# adafruit_oled_featherwing.net
KiCad netlist of a schematic drawn in EAGLE
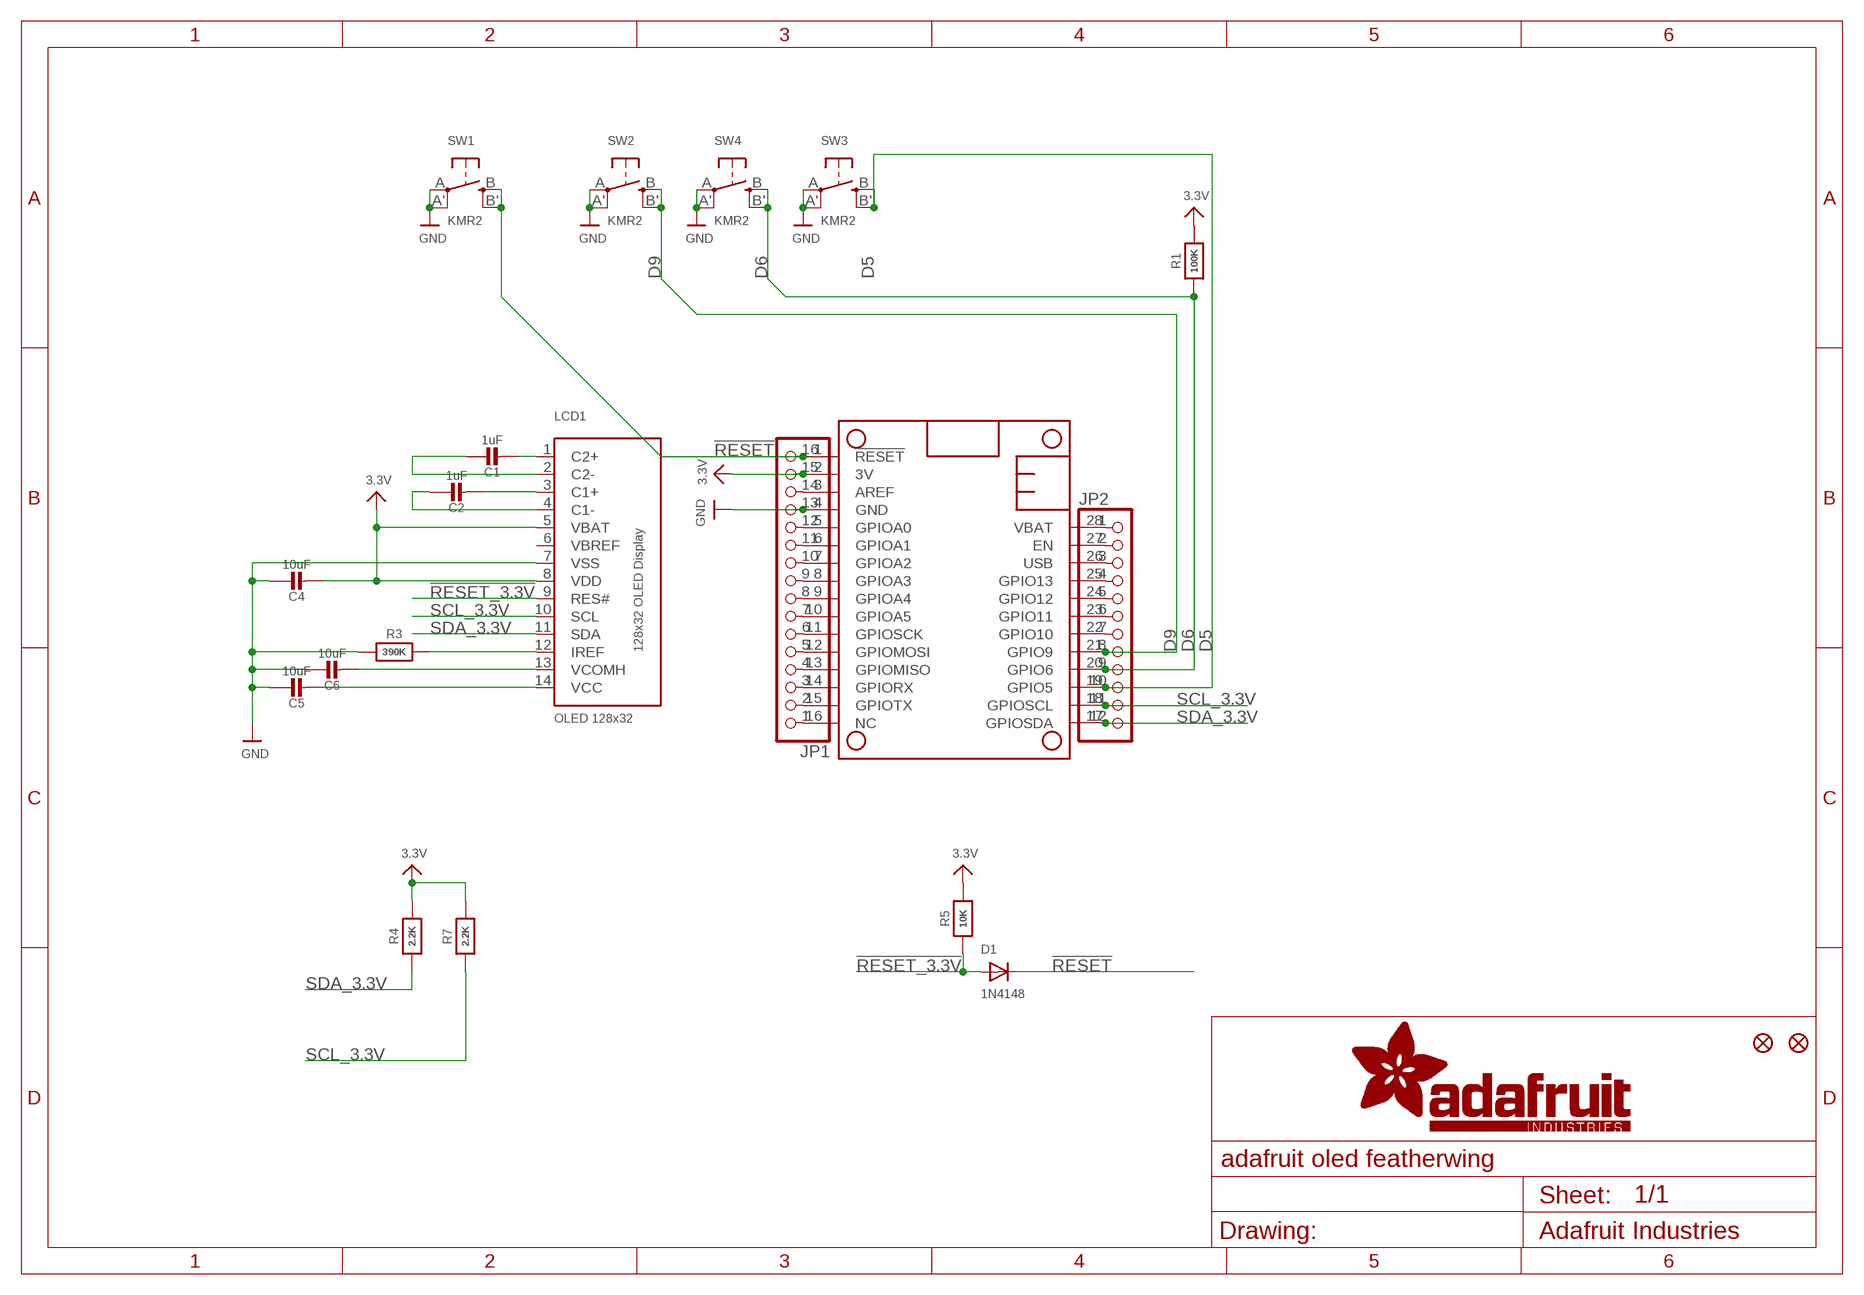
[diagram p0: schematic, sheet 1]

(export (version "E")
  (design (tool "Eeschema 10.0.6"))
  (components
    (comp (ref "C1")
      (value "1uF")
      (footprint "eagle-import:0805-NO")
      (libsource (lib "eagle-import") (part "CAP_CERAMIC0805-NOOUTLINE"))
    )
    (comp (ref "C2")
      (value "1uF")
      (footprint "eagle-import:0805-NO")
      (libsource (lib "eagle-import") (part "CAP_CERAMIC0805-NOOUTLINE"))
    )
    (comp (ref "C4")
      (value "10uF")
      (footprint "eagle-import:0805-NO")
      (libsource (lib "eagle-import") (part "CAP_CERAMIC0805-NOOUTLINE"))
    )
    (comp (ref "C5")
      (value "10uF")
      (footprint "eagle-import:0805-NO")
      (libsource (lib "eagle-import") (part "CAP_CERAMIC0805-NOOUTLINE"))
    )
    (comp (ref "C6")
      (value "10uF")
      (footprint "eagle-import:0805-NO")
      (libsource (lib "eagle-import") (part "CAP_CERAMIC0805-NOOUTLINE"))
    )
    (comp (ref "D1")
      (value "1N4148")
      (footprint "eagle-import:SOD-323F")
      (libsource (lib "eagle-import") (part "DIODESOD-323F"))
    )
    (comp (ref "FID1")
      (value "FIDUCIAL\"\"")
      (footprint "eagle-import:FIDUCIAL_1MM")
      (libsource (lib "eagle-import") (part "FIDUCIAL{dblquote}{dblquote}"))
    )
    (comp (ref "FID2")
      (value "FIDUCIAL\"\"")
      (footprint "eagle-import:FIDUCIAL_1MM")
      (libsource (lib "eagle-import") (part "FIDUCIAL{dblquote}{dblquote}"))
    )
    (comp (ref "JP1")
      (value "HEADER-1X16ROUND")
      (footprint "eagle-import:1X16_ROUND")
      (libsource (lib "eagle-import") (part "HEADER-1X16ROUND"))
    )
    (comp (ref "JP2")
      (value "HEADER-1X12")
      (footprint "eagle-import:1X12_ROUND")
      (libsource (lib "eagle-import") (part "HEADER-1X12"))
    )
    (comp (ref "LCD1")
      (value "OLED 128x32")
      (footprint "eagle-import:UG-2832HSWEG02_WRAPUNDER")
      (libsource (lib "eagle-import") (part "DISP_OLED_UG-2832HSWEG02"))
    )
    (comp (ref "MS1")
      (value "FEATHERWING")
      (footprint "eagle-import:FEATHERWING")
      (libsource (lib "eagle-import") (part "FEATHERWING"))
    )
    (comp (ref "R1")
      (value "100K")
      (footprint "eagle-import:_0805MP")
      (libsource (lib "eagle-import") (part "RESISTOR_0805MP"))
    )
    (comp (ref "R3")
      (value "390K")
      (footprint "eagle-import:0805-NO")
      (libsource (lib "eagle-import") (part "RESISTOR0805_NOOUTLINE"))
    )
    (comp (ref "R4")
      (value "2.2K")
      (footprint "eagle-import:0805-NO")
      (libsource (lib "eagle-import") (part "RESISTOR0805_NOOUTLINE"))
    )
    (comp (ref "R5")
      (value "10K")
      (footprint "eagle-import:0805-NO")
      (libsource (lib "eagle-import") (part "RESISTOR0805_NOOUTLINE"))
    )
    (comp (ref "R7")
      (value "2.2K")
      (footprint "eagle-import:0805-NO")
      (libsource (lib "eagle-import") (part "RESISTOR0805_NOOUTLINE"))
    )
    (comp (ref "SW1")
      (value "KMR2")
      (footprint "eagle-import:BTN_KMR2_4.6X2.8")
      (libsource (lib "eagle-import") (part "SWITCH_TACT_SMT4.6X2.8"))
    )
    (comp (ref "SW2")
      (value "KMR2")
      (footprint "eagle-import:BTN_KMR2_4.6X2.8")
      (libsource (lib "eagle-import") (part "SWITCH_TACT_SMT4.6X2.8"))
    )
    (comp (ref "SW3")
      (value "KMR2")
      (footprint "eagle-import:BTN_KMR2_4.6X2.8")
      (libsource (lib "eagle-import") (part "SWITCH_TACT_SMT4.6X2.8"))
    )
    (comp (ref "SW4")
      (value "KMR2")
      (footprint "eagle-import:BTN_KMR2_4.6X2.8")
      (libsource (lib "eagle-import") (part "SWITCH_TACT_SMT4.6X2.8"))
    )
  )
  (nets
    (net (code "1") (name "/D5") (class "Default")
      (node (ref "JP2") (pin "10") (pinfunction "10_10") (pintype "passive"))
      (node (ref "MS1") (pin "19") (pinfunction "GPIO5_19") (pintype "bidirectional"))
      (node (ref "SW3") (pin "B") (pinfunction "S_B") (pintype "passive"))
      (node (ref "SW3") (pin "B'") (pinfunction "S1_B'") (pintype "passive"))
    )
    (net (code "2") (name "/D6") (class "Default")
      (node (ref "JP2") (pin "9") (pinfunction "9_9") (pintype "passive"))
      (node (ref "MS1") (pin "20") (pinfunction "GPIO6_20") (pintype "bidirectional"))
      (node (ref "R1") (pin "1") (pinfunction "1_1") (pintype "passive"))
      (node (ref "SW4") (pin "B") (pinfunction "S_B") (pintype "passive"))
      (node (ref "SW4") (pin "B'") (pinfunction "S1_B'") (pintype "passive"))
    )
    (net (code "3") (name "/D9") (class "Default")
      (node (ref "JP2") (pin "8") (pinfunction "8_8") (pintype "passive"))
      (node (ref "MS1") (pin "21") (pinfunction "GPIO9_21") (pintype "bidirectional"))
      (node (ref "SW2") (pin "B") (pinfunction "S_B") (pintype "passive"))
      (node (ref "SW2") (pin "B'") (pinfunction "S1_B'") (pintype "passive"))
    )
    (net (code "4") (name "/SCL_3.3V") (class "Default")
      (node (ref "JP2") (pin "11") (pinfunction "11_11") (pintype "passive"))
      (node (ref "LCD1") (pin "10") (pinfunction "SCL_10") (pintype "bidirectional"))
      (node (ref "MS1") (pin "18") (pinfunction "GPIOSCL_18") (pintype "bidirectional"))
      (node (ref "R7") (pin "1") (pinfunction "1_1") (pintype "passive"))
    )
    (net (code "5") (name "/SDA_3.3V") (class "Default")
      (node (ref "JP2") (pin "12") (pinfunction "12_12") (pintype "passive"))
      (node (ref "LCD1") (pin "11") (pinfunction "SDA_11") (pintype "bidirectional"))
      (node (ref "MS1") (pin "17") (pinfunction "GPIOSDA_17") (pintype "bidirectional"))
      (node (ref "R4") (pin "1") (pinfunction "1_1") (pintype "passive"))
    )
    (net (code "6") (name "/VBREF") (class "Default")
      (node (ref "LCD1") (pin "6") (pinfunction "VBREF_6") (pintype "power_in"))
    )
    (net (code "7") (name "/~{RESET_3.3V}") (class "Default")
      (node (ref "D1") (pin "A") (pinfunction "A_A") (pintype "passive"))
      (node (ref "LCD1") (pin "9") (pinfunction "RES#_9") (pintype "bidirectional"))
      (node (ref "R5") (pin "1") (pinfunction "1_1") (pintype "passive"))
    )
    (net (code "8") (name "/~{RESET}") (class "Default")
      (node (ref "D1") (pin "C") (pinfunction "C_C") (pintype "passive"))
      (node (ref "JP1") (pin "16") (pinfunction "16_16") (pintype "passive"))
      (node (ref "MS1") (pin "1") (pinfunction "~{RESET}_1") (pintype "input"))
      (node (ref "SW1") (pin "B") (pinfunction "S_B") (pintype "passive"))
      (node (ref "SW1") (pin "B'") (pinfunction "S1_B'") (pintype "passive"))
    )
    (net (code "9") (name "3.3V") (class "Default")
      (node (ref "C4") (pin "2") (pinfunction "2_2") (pintype "passive"))
      (node (ref "JP1") (pin "15") (pinfunction "15_15") (pintype "passive"))
      (node (ref "LCD1") (pin "5") (pinfunction "VBAT_5") (pintype "power_in"))
      (node (ref "LCD1") (pin "8") (pinfunction "VDD_8") (pintype "power_in"))
      (node (ref "MS1") (pin "2") (pinfunction "3V_2") (pintype "power_in"))
      (node (ref "R1") (pin "2") (pinfunction "2_2") (pintype "passive"))
      (node (ref "R4") (pin "2") (pinfunction "2_2") (pintype "passive"))
      (node (ref "R5") (pin "2") (pinfunction "2_2") (pintype "passive"))
      (node (ref "R7") (pin "2") (pinfunction "2_2") (pintype "passive"))
    )
    (net (code "10") (name "GND") (class "Default")
      (node (ref "C4") (pin "1") (pinfunction "1_1") (pintype "passive"))
      (node (ref "C5") (pin "1") (pinfunction "1_1") (pintype "passive"))
      (node (ref "C6") (pin "1") (pinfunction "1_1") (pintype "passive"))
      (node (ref "JP1") (pin "13") (pinfunction "13_13") (pintype "passive"))
      (node (ref "LCD1") (pin "7") (pinfunction "VSS_7") (pintype "power_in"))
      (node (ref "MS1") (pin "4") (pinfunction "GND_4") (pintype "power_in"))
      (node (ref "R3") (pin "1") (pinfunction "1_1") (pintype "passive"))
      (node (ref "SW1") (pin "A") (pinfunction "P_A") (pintype "passive"))
      (node (ref "SW1") (pin "A'") (pinfunction "P1_A'") (pintype "passive"))
      (node (ref "SW2") (pin "A") (pinfunction "P_A") (pintype "passive"))
      (node (ref "SW2") (pin "A'") (pinfunction "P1_A'") (pintype "passive"))
      (node (ref "SW3") (pin "A") (pinfunction "P_A") (pintype "passive"))
      (node (ref "SW3") (pin "A'") (pinfunction "P1_A'") (pintype "passive"))
      (node (ref "SW4") (pin "A") (pinfunction "P_A") (pintype "passive"))
      (node (ref "SW4") (pin "A'") (pinfunction "P1_A'") (pintype "passive"))
    )
    (net (code "11") (name "Net-(LCD1-C1+)") (class "Default")
      (node (ref "C2") (pin "2") (pinfunction "2_2") (pintype "passive"))
      (node (ref "LCD1") (pin "3") (pinfunction "C1+_3") (pintype "bidirectional"))
    )
    (net (code "12") (name "Net-(LCD1-C1-)") (class "Default")
      (node (ref "C2") (pin "1") (pinfunction "1_1") (pintype "passive"))
      (node (ref "LCD1") (pin "4") (pinfunction "C1-_4") (pintype "bidirectional"))
    )
    (net (code "13") (name "Net-(LCD1-C2+)") (class "Default")
      (node (ref "C1") (pin "2") (pinfunction "2_2") (pintype "passive"))
      (node (ref "LCD1") (pin "1") (pinfunction "C2+_1") (pintype "bidirectional"))
    )
    (net (code "14") (name "Net-(LCD1-C2-)") (class "Default")
      (node (ref "C1") (pin "1") (pinfunction "1_1") (pintype "passive"))
      (node (ref "LCD1") (pin "2") (pinfunction "C2-_2") (pintype "bidirectional"))
    )
    (net (code "15") (name "Net-(LCD1-IREF)") (class "Default")
      (node (ref "LCD1") (pin "12") (pinfunction "IREF_12") (pintype "bidirectional"))
      (node (ref "R3") (pin "2") (pinfunction "2_2") (pintype "passive"))
    )
    (net (code "16") (name "Net-(LCD1-VCC)") (class "Default")
      (node (ref "C5") (pin "2") (pinfunction "2_2") (pintype "passive"))
      (node (ref "LCD1") (pin "14") (pinfunction "VCC_14") (pintype "power_in"))
    )
    (net (code "17") (name "Net-(LCD1-VCOMH)") (class "Default")
      (node (ref "C6") (pin "2") (pinfunction "2_2") (pintype "passive"))
      (node (ref "LCD1") (pin "13") (pinfunction "VCOMH_13") (pintype "power_in"))
    )
    (net (code "18") (name "Net-(MS1-AREF)") (class "Default")
      (node (ref "JP1") (pin "14") (pinfunction "14_14") (pintype "passive"))
      (node (ref "MS1") (pin "3") (pinfunction "AREF_3") (pintype "passive"))
    )
    (net (code "19") (name "Net-(MS1-EN)") (class "Default")
      (node (ref "JP2") (pin "2") (pinfunction "2_2") (pintype "passive"))
      (node (ref "MS1") (pin "27") (pinfunction "EN_27") (pintype "passive"))
    )
    (net (code "20") (name "Net-(MS1-GPIO10)") (class "Default")
      (node (ref "JP2") (pin "7") (pinfunction "7_7") (pintype "passive"))
      (node (ref "MS1") (pin "22") (pinfunction "GPIO10_22") (pintype "bidirectional"))
    )
    (net (code "21") (name "Net-(MS1-GPIO11)") (class "Default")
      (node (ref "JP2") (pin "6") (pinfunction "6_6") (pintype "passive"))
      (node (ref "MS1") (pin "23") (pinfunction "GPIO11_23") (pintype "bidirectional"))
    )
    (net (code "22") (name "Net-(MS1-GPIO12)") (class "Default")
      (node (ref "JP2") (pin "5") (pinfunction "5_5") (pintype "passive"))
      (node (ref "MS1") (pin "24") (pinfunction "GPIO12_24") (pintype "bidirectional"))
    )
    (net (code "23") (name "Net-(MS1-GPIO13)") (class "Default")
      (node (ref "JP2") (pin "4") (pinfunction "4_4") (pintype "passive"))
      (node (ref "MS1") (pin "25") (pinfunction "GPIO13_25") (pintype "bidirectional"))
    )
    (net (code "24") (name "Net-(MS1-GPIOA0)") (class "Default")
      (node (ref "JP1") (pin "12") (pinfunction "12_12") (pintype "passive"))
      (node (ref "MS1") (pin "5") (pinfunction "GPIOA0_5") (pintype "bidirectional"))
    )
    (net (code "25") (name "Net-(MS1-GPIOA1)") (class "Default")
      (node (ref "JP1") (pin "11") (pinfunction "11_11") (pintype "passive"))
      (node (ref "MS1") (pin "6") (pinfunction "GPIOA1_6") (pintype "bidirectional"))
    )
    (net (code "26") (name "Net-(MS1-GPIOA2)") (class "Default")
      (node (ref "JP1") (pin "10") (pinfunction "10_10") (pintype "passive"))
      (node (ref "MS1") (pin "7") (pinfunction "GPIOA2_7") (pintype "bidirectional"))
    )
    (net (code "27") (name "Net-(MS1-GPIOA3)") (class "Default")
      (node (ref "JP1") (pin "9") (pinfunction "9_9") (pintype "passive"))
      (node (ref "MS1") (pin "8") (pinfunction "GPIOA3_8") (pintype "bidirectional"))
    )
    (net (code "28") (name "Net-(MS1-GPIOA4)") (class "Default")
      (node (ref "JP1") (pin "8") (pinfunction "8_8") (pintype "passive"))
      (node (ref "MS1") (pin "9") (pinfunction "GPIOA4_9") (pintype "bidirectional"))
    )
    (net (code "29") (name "Net-(MS1-GPIOA5)") (class "Default")
      (node (ref "JP1") (pin "7") (pinfunction "7_7") (pintype "passive"))
      (node (ref "MS1") (pin "10") (pinfunction "GPIOA5_10") (pintype "bidirectional"))
    )
    (net (code "30") (name "Net-(MS1-GPIOMISO)") (class "Default")
      (node (ref "JP1") (pin "4") (pinfunction "4_4") (pintype "passive"))
      (node (ref "MS1") (pin "13") (pinfunction "GPIOMISO_13") (pintype "bidirectional"))
    )
    (net (code "31") (name "Net-(MS1-GPIOMOSI)") (class "Default")
      (node (ref "JP1") (pin "5") (pinfunction "5_5") (pintype "passive"))
      (node (ref "MS1") (pin "12") (pinfunction "GPIOMOSI_12") (pintype "bidirectional"))
    )
    (net (code "32") (name "Net-(MS1-GPIORX)") (class "Default")
      (node (ref "JP1") (pin "3") (pinfunction "3_3") (pintype "passive"))
      (node (ref "MS1") (pin "14") (pinfunction "GPIORX_14") (pintype "bidirectional"))
    )
    (net (code "33") (name "Net-(MS1-GPIOSCK)") (class "Default")
      (node (ref "JP1") (pin "6") (pinfunction "6_6") (pintype "passive"))
      (node (ref "MS1") (pin "11") (pinfunction "GPIOSCK_11") (pintype "bidirectional"))
    )
    (net (code "34") (name "Net-(MS1-GPIOTX)") (class "Default")
      (node (ref "JP1") (pin "2") (pinfunction "2_2") (pintype "passive"))
      (node (ref "MS1") (pin "15") (pinfunction "GPIOTX_15") (pintype "bidirectional"))
    )
    (net (code "35") (name "Net-(MS1-NC)") (class "Default")
      (node (ref "JP1") (pin "1") (pinfunction "1_1") (pintype "passive"))
      (node (ref "MS1") (pin "16") (pinfunction "NC_16") (pintype "passive"))
    )
    (net (code "36") (name "Net-(MS1-USB)") (class "Default")
      (node (ref "JP2") (pin "3") (pinfunction "3_3") (pintype "passive"))
      (node (ref "MS1") (pin "26") (pinfunction "USB_26") (pintype "power_in"))
    )
    (net (code "37") (name "Net-(MS1-VBAT)") (class "Default")
      (node (ref "JP2") (pin "1") (pinfunction "1_1") (pintype "passive"))
      (node (ref "MS1") (pin "28") (pinfunction "VBAT_28") (pintype "power_in"))
    )
  )
)
